# breakout.net
KiCad netlist of a schematic drawn in EAGLE
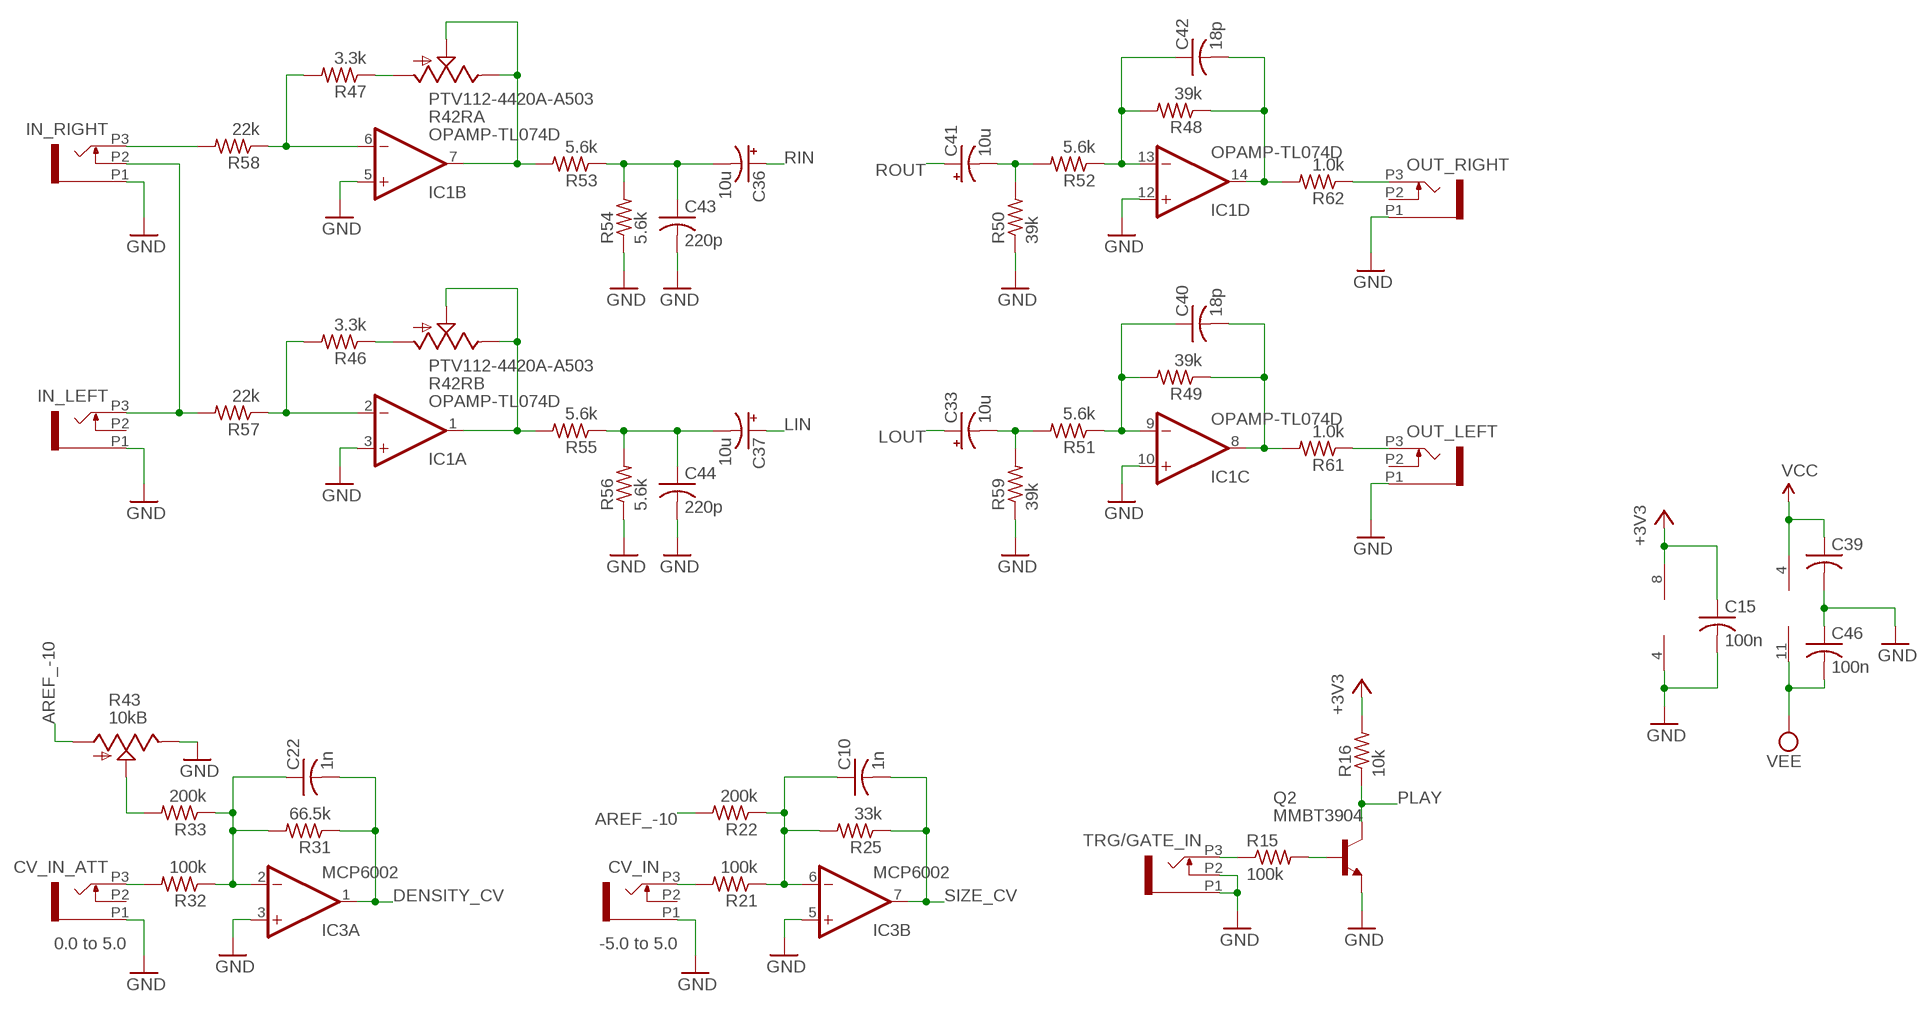
[diagram p0: schematic, sheet 1]
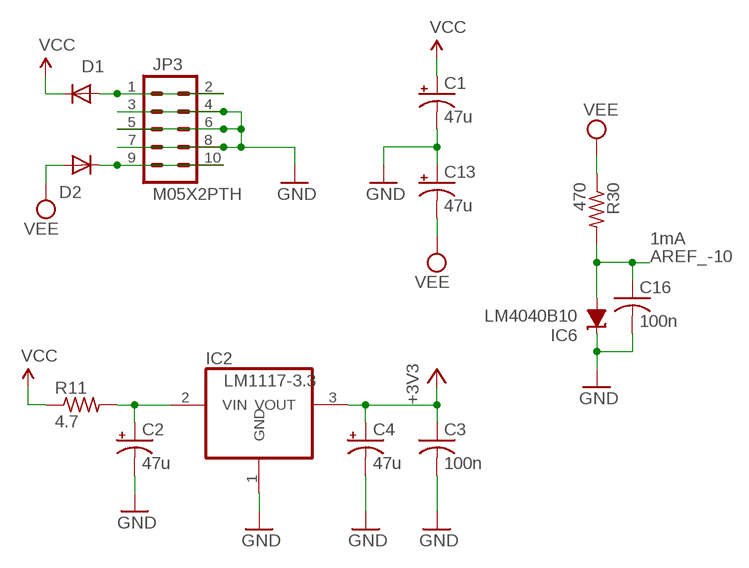
[diagram p1: schematic, sheet 2]

(export (version "E")
  (design (tool "Eeschema 10.0.6"))
  (components
    (comp (ref "C1")
      (value "47u")
      (footprint "eagle-import:PANASONIC_D")
      (libsource (lib "eagle-import") (part "CPOL-USD"))
    )
    (comp (ref "C2")
      (value "47u")
      (footprint "eagle-import:PANASONIC_D")
      (libsource (lib "eagle-import") (part "CPOL-USD"))
    )
    (comp (ref "C3")
      (value "100n")
      (footprint "eagle-import:C0603")
      (libsource (lib "eagle-import") (part "C-USC0603"))
    )
    (comp (ref "C4")
      (value "47u")
      (footprint "eagle-import:PANASONIC_D")
      (libsource (lib "eagle-import") (part "CPOL-USD"))
    )
    (comp (ref "C13")
      (value "47u")
      (footprint "eagle-import:PANASONIC_D")
      (libsource (lib "eagle-import") (part "CPOL-USD"))
    )
    (comp (ref "C16")
      (value "100n")
      (footprint "eagle-import:C0603")
      (libsource (lib "eagle-import") (part "C-USC0603"))
    )
    (comp (ref "D1")
      (value "1N5819HW")
      (footprint "eagle-import:SOD123")
      (libsource (lib "eagle-import") (part "DIODE-SOD123"))
    )
    (comp (ref "D2")
      (value "1N5819HW")
      (footprint "eagle-import:SOD123")
      (libsource (lib "eagle-import") (part "DIODE-SOD123"))
    )
    (comp (ref "IC2")
      (value "LM1117-3.3")
      (footprint "eagle-import:TO252")
      (libsource (lib "eagle-import") (part "REG1117T"))
    )
    (comp (ref "IC6")
      (value "LM4040B10")
      (footprint "eagle-import:DBZ_R-PDSO-G3")
      (libsource (lib "eagle-import") (part "LM4041DBZB12"))
    )
    (comp (ref "JP3")
      (value "M05X2PTH")
      (footprint "eagle-import:AVR_ICSP")
      (libsource (lib "eagle-import") (part "M05X2PTH"))
    )
    (comp (ref "R11")
      (value "4.7")
      (footprint "eagle-import:R1206")
      (libsource (lib "eagle-import") (part "R-US_R1206"))
    )
    (comp (ref "R30")
      (value "470")
      (footprint "eagle-import:R0603")
      (libsource (lib "eagle-import") (part "R-US_R0603"))
    )
    (comp (ref "C10")
      (value "1n")
      (footprint "eagle-import:C0603")
      (libsource (lib "eagle-import") (part "C-USC0603"))
    )
    (comp (ref "C15")
      (value "100n")
      (footprint "eagle-import:C0603")
      (libsource (lib "eagle-import") (part "C-USC0603"))
    )
    (comp (ref "C22")
      (value "1n")
      (footprint "eagle-import:C0603")
      (libsource (lib "eagle-import") (part "C-USC0603"))
    )
    (comp (ref "C33")
      (value "10u")
      (footprint "eagle-import:PANASONIC_B")
      (libsource (lib "eagle-import") (part "CPOL-USB"))
    )
    (comp (ref "C36")
      (value "10u")
      (footprint "eagle-import:PANASONIC_B")
      (libsource (lib "eagle-import") (part "CPOL-USB"))
    )
    (comp (ref "C37")
      (value "10u")
      (footprint "eagle-import:PANASONIC_B")
      (libsource (lib "eagle-import") (part "CPOL-USB"))
    )
    (comp (ref "C39")
      (value "100n")
      (footprint "eagle-import:C0603")
      (libsource (lib "eagle-import") (part "C-USC0603"))
    )
    (comp (ref "C40")
      (value "18p")
      (footprint "eagle-import:C0603")
      (libsource (lib "eagle-import") (part "C-USC0603"))
    )
    (comp (ref "C41")
      (value "10u")
      (footprint "eagle-import:PANASONIC_B")
      (libsource (lib "eagle-import") (part "CPOL-USB"))
    )
    (comp (ref "C42")
      (value "18p")
      (footprint "eagle-import:C0603")
      (libsource (lib "eagle-import") (part "C-USC0603"))
    )
    (comp (ref "C43")
      (value "220p")
      (footprint "eagle-import:C0603")
      (libsource (lib "eagle-import") (part "C-USC0603"))
    )
    (comp (ref "C44")
      (value "220p")
      (footprint "eagle-import:C0603")
      (libsource (lib "eagle-import") (part "C-USC0603"))
    )
    (comp (ref "C46")
      (value "100n")
      (footprint "eagle-import:C0603")
      (libsource (lib "eagle-import") (part "C-USC0603"))
    )
    (comp (ref "CV_IN")
      (value "PJ301_THONKICONN6")
      (footprint "eagle-import:WQP_PJ_301M6")
      (libsource (lib "eagle-import") (part "PJ301_THONKICONN6"))
    )
    (comp (ref "CV_IN_ATT")
      (value "PJ301_THONKICONN6")
      (footprint "eagle-import:WQP_PJ_301M6")
      (libsource (lib "eagle-import") (part "PJ301_THONKICONN6"))
    )
    (comp (ref "IC1")
      (value "OPAMP-TL074D")
      (footprint "eagle-import:SO14")
      (libsource (lib "eagle-import") (part "OPAMP-TL074D"))
    )
    (comp (ref "IC3")
      (value "MCP6002")
      (footprint "eagle-import:SO08")
      (libsource (lib "eagle-import") (part "TL072D"))
    )
    (comp (ref "IN_LEFT")
      (value "PJ301_THONKICONN6")
      (footprint "eagle-import:WQP_PJ_301M6")
      (libsource (lib "eagle-import") (part "PJ301_THONKICONN6"))
    )
    (comp (ref "IN_RIGHT")
      (value "PJ301_THONKICONN6")
      (footprint "eagle-import:WQP_PJ_301M6")
      (libsource (lib "eagle-import") (part "PJ301_THONKICONN6"))
    )
    (comp (ref "OUT_LEFT")
      (value "PJ301_THONKICONN6")
      (footprint "eagle-import:WQP_PJ_301M6")
      (libsource (lib "eagle-import") (part "PJ301_THONKICONN6"))
    )
    (comp (ref "OUT_RIGHT")
      (value "PJ301_THONKICONN6")
      (footprint "eagle-import:WQP_PJ_301M6")
      (libsource (lib "eagle-import") (part "PJ301_THONKICONN6"))
    )
    (comp (ref "Q2")
      (value "MMBT3904")
      (footprint "eagle-import:SOT23-BEC")
      (libsource (lib "eagle-import") (part "-NPN-SOT23-BECMMBT3904LT1"))
    )
    (comp (ref "R15")
      (value "100k")
      (footprint "eagle-import:R0603")
      (libsource (lib "eagle-import") (part "R-US_R0603"))
    )
    (comp (ref "R16")
      (value "10k")
      (footprint "eagle-import:R0603")
      (libsource (lib "eagle-import") (part "R-US_R0603"))
    )
    (comp (ref "R21")
      (value "100k")
      (footprint "eagle-import:R0603")
      (libsource (lib "eagle-import") (part "R-US_R0603"))
    )
    (comp (ref "R22")
      (value "200k")
      (footprint "eagle-import:R0603")
      (libsource (lib "eagle-import") (part "R-US_R0603"))
    )
    (comp (ref "R25")
      (value "33k")
      (footprint "eagle-import:R0603")
      (libsource (lib "eagle-import") (part "R-US_R0603"))
    )
    (comp (ref "R31")
      (value "66.5k")
      (footprint "eagle-import:R0603")
      (libsource (lib "eagle-import") (part "R-US_R0603"))
    )
    (comp (ref "R32")
      (value "100k")
      (footprint "eagle-import:R0603")
      (libsource (lib "eagle-import") (part "R-US_R0603"))
    )
    (comp (ref "R33")
      (value "200k")
      (footprint "eagle-import:R0603")
      (libsource (lib "eagle-import") (part "R-US_R0603"))
    )
    (comp (ref "R42")
      (value "PTV112-4420A-A503")
      (footprint "eagle-import:BOURNS_PTV112")
      (libsource (lib "eagle-import") (part "POT_US_DUAL_GANG"))
    )
    (comp (ref "R43")
      (value "10kB")
      (footprint "eagle-import:ALPS_POT_VERTICAL_PS")
      (libsource (lib "eagle-import") (part "POT_USVERTICAL_PS"))
    )
    (comp (ref "R46")
      (value "3.3k")
      (footprint "eagle-import:R0603")
      (libsource (lib "eagle-import") (part "R-US_R0603"))
    )
    (comp (ref "R47")
      (value "3.3k")
      (footprint "eagle-import:R0603")
      (libsource (lib "eagle-import") (part "R-US_R0603"))
    )
    (comp (ref "R48")
      (value "39k")
      (footprint "eagle-import:R0603")
      (libsource (lib "eagle-import") (part "R-US_R0603"))
    )
    (comp (ref "R49")
      (value "39k")
      (footprint "eagle-import:R0603")
      (libsource (lib "eagle-import") (part "R-US_R0603"))
    )
    (comp (ref "R50")
      (value "39k")
      (footprint "eagle-import:R0603")
      (libsource (lib "eagle-import") (part "R-US_R0603"))
    )
    (comp (ref "R51")
      (value "5.6k")
      (footprint "eagle-import:R0603")
      (libsource (lib "eagle-import") (part "R-US_R0603"))
    )
    (comp (ref "R52")
      (value "5.6k")
      (footprint "eagle-import:R0603")
      (libsource (lib "eagle-import") (part "R-US_R0603"))
    )
    (comp (ref "R53")
      (value "5.6k")
      (footprint "eagle-import:R0603")
      (libsource (lib "eagle-import") (part "R-US_R0603"))
    )
    (comp (ref "R54")
      (value "5.6k")
      (footprint "eagle-import:R0603")
      (libsource (lib "eagle-import") (part "R-US_R0603"))
    )
    (comp (ref "R55")
      (value "5.6k")
      (footprint "eagle-import:R0603")
      (libsource (lib "eagle-import") (part "R-US_R0603"))
    )
    (comp (ref "R56")
      (value "5.6k")
      (footprint "eagle-import:R0603")
      (libsource (lib "eagle-import") (part "R-US_R0603"))
    )
    (comp (ref "R57")
      (value "22k")
      (footprint "eagle-import:R0603")
      (libsource (lib "eagle-import") (part "R-US_R0603"))
    )
    (comp (ref "R58")
      (value "22k")
      (footprint "eagle-import:R0603")
      (libsource (lib "eagle-import") (part "R-US_R0603"))
    )
    (comp (ref "R59")
      (value "39k")
      (footprint "eagle-import:R0603")
      (libsource (lib "eagle-import") (part "R-US_R0603"))
    )
    (comp (ref "R61")
      (value "1.0k")
      (footprint "eagle-import:R0603")
      (libsource (lib "eagle-import") (part "R-US_R0603"))
    )
    (comp (ref "R62")
      (value "1.0k")
      (footprint "eagle-import:R0603")
      (libsource (lib "eagle-import") (part "R-US_R0603"))
    )
    (comp (ref "TRG/GATE_IN")
      (value "PJ301_THONKICONN6")
      (footprint "eagle-import:WQP_PJ_301M6")
      (libsource (lib "eagle-import") (part "PJ301_THONKICONN6"))
    )
  )
  (nets
    (net (code "1") (name "+3V3") (class "Default")
      (node (ref "C15") (pin "1") (pinfunction "1_1") (pintype "passive"))
      (node (ref "C3") (pin "1") (pinfunction "1_1") (pintype "passive"))
      (node (ref "C4") (pin "+") (pinfunction "+_+") (pintype "passive"))
      (node (ref "IC2") (pin "3") (pinfunction "VOUT_3") (pintype "output"))
      (node (ref "IC3") (pin "8") (pinfunction "V+_8") (pintype "power_in"))
      (node (ref "R16") (pin "2") (pinfunction "2_2") (pintype "passive"))
    )
    (net (code "2") (name "AREF_-10") (class "Default")
      (node (ref "C16") (pin "1") (pinfunction "1_1") (pintype "passive"))
      (node (ref "IC6") (pin "2") (pinfunction "A_2") (pintype "passive"))
      (node (ref "R22") (pin "2") (pinfunction "2_2") (pintype "passive"))
      (node (ref "R30") (pin "2") (pinfunction "2_2") (pintype "passive"))
      (node (ref "R43") (pin "P$3") (pinfunction "A_P$3") (pintype "passive"))
    )
    (net (code "3") (name "DENSITY_CV") (class "Default")
      (node (ref "C22") (pin "2") (pinfunction "2_2") (pintype "passive"))
      (node (ref "IC3") (pin "1") (pinfunction "OUT_1") (pintype "output"))
      (node (ref "R31") (pin "1") (pinfunction "1_1") (pintype "passive"))
    )
    (net (code "4") (name "GND") (class "Default")
      (node (ref "C1") (pin "-") (pinfunction "-_-") (pintype "passive"))
      (node (ref "C13") (pin "+") (pinfunction "+_+") (pintype "passive"))
      (node (ref "C15") (pin "2") (pinfunction "2_2") (pintype "passive"))
      (node (ref "C16") (pin "2") (pinfunction "2_2") (pintype "passive"))
      (node (ref "C2") (pin "-") (pinfunction "-_-") (pintype "passive"))
      (node (ref "C3") (pin "2") (pinfunction "2_2") (pintype "passive"))
      (node (ref "C39") (pin "2") (pinfunction "2_2") (pintype "passive"))
      (node (ref "C4") (pin "-") (pinfunction "-_-") (pintype "passive"))
      (node (ref "C43") (pin "2") (pinfunction "2_2") (pintype "passive"))
      (node (ref "C44") (pin "2") (pinfunction "2_2") (pintype "passive"))
      (node (ref "C46") (pin "1") (pinfunction "1_1") (pintype "passive"))
      (node (ref "CV_IN") (pin "P1") (pinfunction "1_P1") (pintype "passive"))
      (node (ref "CV_IN_ATT") (pin "P1") (pinfunction "1_P1") (pintype "passive"))
      (node (ref "IC1") (pin "10") (pinfunction "+IN_10") (pintype "input"))
      (node (ref "IC1") (pin "12") (pinfunction "+IN_12") (pintype "input"))
      (node (ref "IC1") (pin "3") (pinfunction "+IN_3") (pintype "input"))
      (node (ref "IC1") (pin "5") (pinfunction "+IN_5") (pintype "input"))
      (node (ref "IC2") (pin "1") (pinfunction "GND_1") (pintype "power_in"))
      (node (ref "IC3") (pin "3") (pinfunction "+IN_3") (pintype "input"))
      (node (ref "IC3") (pin "4") (pinfunction "V-_4") (pintype "power_in"))
      (node (ref "IC3") (pin "5") (pinfunction "+IN_5") (pintype "input"))
      (node (ref "IC6") (pin "1") (pinfunction "C_1") (pintype "passive"))
      (node (ref "IN_LEFT") (pin "P1") (pinfunction "1_P1") (pintype "passive"))
      (node (ref "IN_RIGHT") (pin "P1") (pinfunction "1_P1") (pintype "passive"))
      (node (ref "JP3") (pin "3") (pinfunction "3_3") (pintype "passive"))
      (node (ref "JP3") (pin "4") (pinfunction "4_4") (pintype "passive"))
      (node (ref "JP3") (pin "5") (pinfunction "5_5") (pintype "passive"))
      (node (ref "JP3") (pin "6") (pinfunction "6_6") (pintype "passive"))
      (node (ref "JP3") (pin "7") (pinfunction "7_7") (pintype "passive"))
      (node (ref "JP3") (pin "8") (pinfunction "8_8") (pintype "passive"))
      (node (ref "OUT_LEFT") (pin "P1") (pinfunction "1_P1") (pintype "passive"))
      (node (ref "OUT_RIGHT") (pin "P1") (pinfunction "1_P1") (pintype "passive"))
      (node (ref "Q2") (pin "E") (pinfunction "E_E") (pintype "passive"))
      (node (ref "R43") (pin "P$1") (pinfunction "E_P$1") (pintype "passive"))
      (node (ref "R50") (pin "1") (pinfunction "1_1") (pintype "passive"))
      (node (ref "R54") (pin "1") (pinfunction "1_1") (pintype "passive"))
      (node (ref "R56") (pin "1") (pinfunction "1_1") (pintype "passive"))
      (node (ref "R59") (pin "1") (pinfunction "1_1") (pintype "passive"))
      (node (ref "TRG/GATE_IN") (pin "P1") (pinfunction "1_P1") (pintype "passive"))
      (node (ref "TRG/GATE_IN") (pin "P2") (pinfunction "2_P2") (pintype "passive"))
    )
    (net (code "5") (name "LIN") (class "Default")
      (node (ref "C37") (pin "+") (pinfunction "+_+") (pintype "passive"))
    )
    (net (code "6") (name "LOUT") (class "Default")
      (node (ref "C33") (pin "+") (pinfunction "+_+") (pintype "passive"))
    )
    (net (code "7") (name "Net-(C33-Pad-)") (class "Default")
      (node (ref "C33") (pin "-") (pinfunction "-_-") (pintype "passive"))
      (node (ref "R51") (pin "2") (pinfunction "2_2") (pintype "passive"))
      (node (ref "R59") (pin "2") (pinfunction "2_2") (pintype "passive"))
    )
    (net (code "8") (name "Net-(C36-Pad-)") (class "Default")
      (node (ref "C36") (pin "-") (pinfunction "-_-") (pintype "passive"))
      (node (ref "C43") (pin "1") (pinfunction "1_1") (pintype "passive"))
      (node (ref "R53") (pin "1") (pinfunction "1_1") (pintype "passive"))
      (node (ref "R54") (pin "2") (pinfunction "2_2") (pintype "passive"))
    )
    (net (code "9") (name "Net-(C37-Pad-)") (class "Default")
      (node (ref "C37") (pin "-") (pinfunction "-_-") (pintype "passive"))
      (node (ref "C44") (pin "1") (pinfunction "1_1") (pintype "passive"))
      (node (ref "R55") (pin "1") (pinfunction "1_1") (pintype "passive"))
      (node (ref "R56") (pin "2") (pinfunction "2_2") (pintype "passive"))
    )
    (net (code "10") (name "Net-(C41-Pad-)") (class "Default")
      (node (ref "C41") (pin "-") (pinfunction "-_-") (pintype "passive"))
      (node (ref "R50") (pin "2") (pinfunction "2_2") (pintype "passive"))
      (node (ref "R52") (pin "2") (pinfunction "2_2") (pintype "passive"))
    )
    (net (code "11") (name "Net-(CV_IN-3)") (class "Default")
      (node (ref "CV_IN") (pin "P3") (pinfunction "3_P3") (pintype "passive"))
      (node (ref "R21") (pin "2") (pinfunction "2_2") (pintype "passive"))
    )
    (net (code "12") (name "Net-(CV_IN_ATT-3)") (class "Default")
      (node (ref "CV_IN_ATT") (pin "P3") (pinfunction "3_P3") (pintype "passive"))
      (node (ref "R32") (pin "2") (pinfunction "2_2") (pintype "passive"))
    )
    (net (code "13") (name "Net-(D1-PadA)") (class "Default")
      (node (ref "D1") (pin "A") (pinfunction "A_A") (pintype "passive"))
      (node (ref "JP3") (pin "1") (pinfunction "1_1") (pintype "passive"))
      (node (ref "JP3") (pin "2") (pinfunction "2_2") (pintype "passive"))
    )
    (net (code "14") (name "Net-(D2-PadC)") (class "Default")
      (node (ref "D2") (pin "C") (pinfunction "C_C") (pintype "passive"))
      (node (ref "JP3") (pin "10") (pinfunction "10_10") (pintype "passive"))
      (node (ref "JP3") (pin "9") (pinfunction "9_9") (pintype "passive"))
    )
    (net (code "15") (name "Net-(IC1A--IN)") (class "Default")
      (node (ref "IC1") (pin "2") (pinfunction "-IN_2") (pintype "input"))
      (node (ref "R46") (pin "2") (pinfunction "2_2") (pintype "passive"))
      (node (ref "R57") (pin "1") (pinfunction "1_1") (pintype "passive"))
    )
    (net (code "16") (name "Net-(IC1A-OUT)") (class "Default")
      (node (ref "IC1") (pin "1") (pinfunction "OUT_1") (pintype "output"))
      (node (ref "R42") (pin "2") (pinfunction "S_2") (pintype "passive"))
      (node (ref "R42") (pin "3") (pinfunction "E_3") (pintype "passive"))
      (node (ref "R55") (pin "2") (pinfunction "2_2") (pintype "passive"))
    )
    (net (code "17") (name "Net-(IC1B--IN)") (class "Default")
      (node (ref "IC1") (pin "6") (pinfunction "-IN_6") (pintype "input"))
      (node (ref "R47") (pin "2") (pinfunction "2_2") (pintype "passive"))
      (node (ref "R58") (pin "1") (pinfunction "1_1") (pintype "passive"))
    )
    (net (code "18") (name "Net-(IC1B-OUT)") (class "Default")
      (node (ref "IC1") (pin "7") (pinfunction "OUT_7") (pintype "output"))
      (node (ref "R42") (pin "2P") (pinfunction "S_2P") (pintype "passive"))
      (node (ref "R42") (pin "3P") (pinfunction "E_3P") (pintype "passive"))
      (node (ref "R53") (pin "2") (pinfunction "2_2") (pintype "passive"))
    )
    (net (code "19") (name "Net-(IC1C--IN)") (class "Default")
      (node (ref "C40") (pin "1") (pinfunction "1_1") (pintype "passive"))
      (node (ref "IC1") (pin "9") (pinfunction "-IN_9") (pintype "input"))
      (node (ref "R49") (pin "2") (pinfunction "2_2") (pintype "passive"))
      (node (ref "R51") (pin "1") (pinfunction "1_1") (pintype "passive"))
    )
    (net (code "20") (name "Net-(IC1C-OUT)") (class "Default")
      (node (ref "C40") (pin "2") (pinfunction "2_2") (pintype "passive"))
      (node (ref "IC1") (pin "8") (pinfunction "OUT_8") (pintype "output"))
      (node (ref "R49") (pin "1") (pinfunction "1_1") (pintype "passive"))
      (node (ref "R61") (pin "2") (pinfunction "2_2") (pintype "passive"))
    )
    (net (code "21") (name "Net-(IC1D--IN)") (class "Default")
      (node (ref "C42") (pin "1") (pinfunction "1_1") (pintype "passive"))
      (node (ref "IC1") (pin "13") (pinfunction "-IN_13") (pintype "input"))
      (node (ref "R48") (pin "2") (pinfunction "2_2") (pintype "passive"))
      (node (ref "R52") (pin "1") (pinfunction "1_1") (pintype "passive"))
    )
    (net (code "22") (name "Net-(IC1D-OUT)") (class "Default")
      (node (ref "C42") (pin "2") (pinfunction "2_2") (pintype "passive"))
      (node (ref "IC1") (pin "14") (pinfunction "OUT_14") (pintype "output"))
      (node (ref "R48") (pin "1") (pinfunction "1_1") (pintype "passive"))
      (node (ref "R62") (pin "2") (pinfunction "2_2") (pintype "passive"))
    )
    (net (code "23") (name "Net-(IC2-VIN)") (class "Default")
      (node (ref "C2") (pin "+") (pinfunction "+_+") (pintype "passive"))
      (node (ref "IC2") (pin "2") (pinfunction "VIN_2") (pintype "input"))
      (node (ref "R11") (pin "2") (pinfunction "2_2") (pintype "passive"))
    )
    (net (code "24") (name "Net-(IC3A--IN)") (class "Default")
      (node (ref "C22") (pin "1") (pinfunction "1_1") (pintype "passive"))
      (node (ref "IC3") (pin "2") (pinfunction "-IN_2") (pintype "input"))
      (node (ref "R31") (pin "2") (pinfunction "2_2") (pintype "passive"))
      (node (ref "R32") (pin "1") (pinfunction "1_1") (pintype "passive"))
      (node (ref "R33") (pin "1") (pinfunction "1_1") (pintype "passive"))
    )
    (net (code "25") (name "Net-(IC3B--IN)") (class "Default")
      (node (ref "C10") (pin "1") (pinfunction "1_1") (pintype "passive"))
      (node (ref "IC3") (pin "6") (pinfunction "-IN_6") (pintype "input"))
      (node (ref "R21") (pin "1") (pinfunction "1_1") (pintype "passive"))
      (node (ref "R22") (pin "1") (pinfunction "1_1") (pintype "passive"))
      (node (ref "R25") (pin "2") (pinfunction "2_2") (pintype "passive"))
    )
    (net (code "26") (name "Net-(IN_LEFT-3)") (class "Default")
      (node (ref "IN_LEFT") (pin "P3") (pinfunction "3_P3") (pintype "passive"))
      (node (ref "IN_RIGHT") (pin "P2") (pinfunction "2_P2") (pintype "passive"))
      (node (ref "R57") (pin "2") (pinfunction "2_2") (pintype "passive"))
    )
    (net (code "27") (name "Net-(IN_RIGHT-3)") (class "Default")
      (node (ref "IN_RIGHT") (pin "P3") (pinfunction "3_P3") (pintype "passive"))
      (node (ref "R58") (pin "2") (pinfunction "2_2") (pintype "passive"))
    )
    (net (code "28") (name "Net-(OUT_LEFT-3)") (class "Default")
      (node (ref "OUT_LEFT") (pin "P3") (pinfunction "3_P3") (pintype "passive"))
      (node (ref "R61") (pin "1") (pinfunction "1_1") (pintype "passive"))
    )
    (net (code "29") (name "Net-(OUT_RIGHT-3)") (class "Default")
      (node (ref "OUT_RIGHT") (pin "P3") (pinfunction "3_P3") (pintype "passive"))
      (node (ref "R62") (pin "1") (pinfunction "1_1") (pintype "passive"))
    )
    (net (code "30") (name "Net-(Q2-PadB)") (class "Default")
      (node (ref "Q2") (pin "B") (pinfunction "B_B") (pintype "passive"))
      (node (ref "R15") (pin "2") (pinfunction "2_2") (pintype "passive"))
    )
    (net (code "31") (name "Net-(R42A-A)") (class "Default")
      (node (ref "R42") (pin "1P") (pinfunction "A_1P") (pintype "passive"))
      (node (ref "R47") (pin "1") (pinfunction "1_1") (pintype "passive"))
    )
    (net (code "32") (name "Net-(R42B-A)") (class "Default")
      (node (ref "R42") (pin "1") (pinfunction "A_1") (pintype "passive"))
      (node (ref "R46") (pin "1") (pinfunction "1_1") (pintype "passive"))
    )
    (net (code "33") (name "Net-(R43-S)") (class "Default")
      (node (ref "R33") (pin "2") (pinfunction "2_2") (pintype "passive"))
      (node (ref "R43") (pin "P$2") (pinfunction "S_P$2") (pintype "passive"))
    )
    (net (code "34") (name "Net-(TRG/GATE_IN-3)") (class "Default")
      (node (ref "R15") (pin "1") (pinfunction "1_1") (pintype "passive"))
      (node (ref "TRG/GATE_IN") (pin "P3") (pinfunction "3_P3") (pintype "passive"))
    )
    (net (code "35") (name "PLAY") (class "Default")
      (node (ref "Q2") (pin "C") (pinfunction "C_C") (pintype "passive"))
      (node (ref "R16") (pin "1") (pinfunction "1_1") (pintype "passive"))
    )
    (net (code "36") (name "RIN") (class "Default")
      (node (ref "C36") (pin "+") (pinfunction "+_+") (pintype "passive"))
    )
    (net (code "37") (name "ROUT") (class "Default")
      (node (ref "C41") (pin "+") (pinfunction "+_+") (pintype "passive"))
    )
    (net (code "38") (name "SIZE_CV") (class "Default")
      (node (ref "C10") (pin "2") (pinfunction "2_2") (pintype "passive"))
      (node (ref "IC3") (pin "7") (pinfunction "OUT_7") (pintype "output"))
      (node (ref "R25") (pin "1") (pinfunction "1_1") (pintype "passive"))
    )
    (net (code "39") (name "VCC") (class "Default")
      (node (ref "C1") (pin "+") (pinfunction "+_+") (pintype "passive"))
      (node (ref "C39") (pin "1") (pinfunction "1_1") (pintype "passive"))
      (node (ref "D1") (pin "C") (pinfunction "C_C") (pintype "passive"))
      (node (ref "IC1") (pin "4") (pinfunction "V+_4") (pintype "power_in"))
      (node (ref "R11") (pin "1") (pinfunction "1_1") (pintype "passive"))
    )
    (net (code "40") (name "VEE") (class "Default")
      (node (ref "C13") (pin "-") (pinfunction "-_-") (pintype "passive"))
      (node (ref "C46") (pin "2") (pinfunction "2_2") (pintype "passive"))
      (node (ref "D2") (pin "A") (pinfunction "A_A") (pintype "passive"))
      (node (ref "IC1") (pin "11") (pinfunction "V-_11") (pintype "power_in"))
      (node (ref "R30") (pin "1") (pinfunction "1_1") (pintype "passive"))
    )
    (net (code "41") (name "unconnected-(CV_IN-2-PadP2)") (class "Default")
      (node (ref "CV_IN") (pin "P2") (pinfunction "2_P2") (pintype "passive"))
    )
    (net (code "42") (name "unconnected-(CV_IN_ATT-2-PadP2)") (class "Default")
      (node (ref "CV_IN_ATT") (pin "P2") (pinfunction "2_P2") (pintype "passive"))
    )
    (net (code "43") (name "unconnected-(IN_LEFT-2-PadP2)") (class "Default")
      (node (ref "IN_LEFT") (pin "P2") (pinfunction "2_P2") (pintype "passive"))
    )
    (net (code "44") (name "unconnected-(OUT_LEFT-2-PadP2)") (class "Default")
      (node (ref "OUT_LEFT") (pin "P2") (pinfunction "2_P2") (pintype "passive"))
    )
    (net (code "45") (name "unconnected-(OUT_RIGHT-2-PadP2)") (class "Default")
      (node (ref "OUT_RIGHT") (pin "P2") (pinfunction "2_P2") (pintype "passive"))
    )
  )
)
